# prominifinal.net
KiCad netlist of a schematic drawn in EAGLE
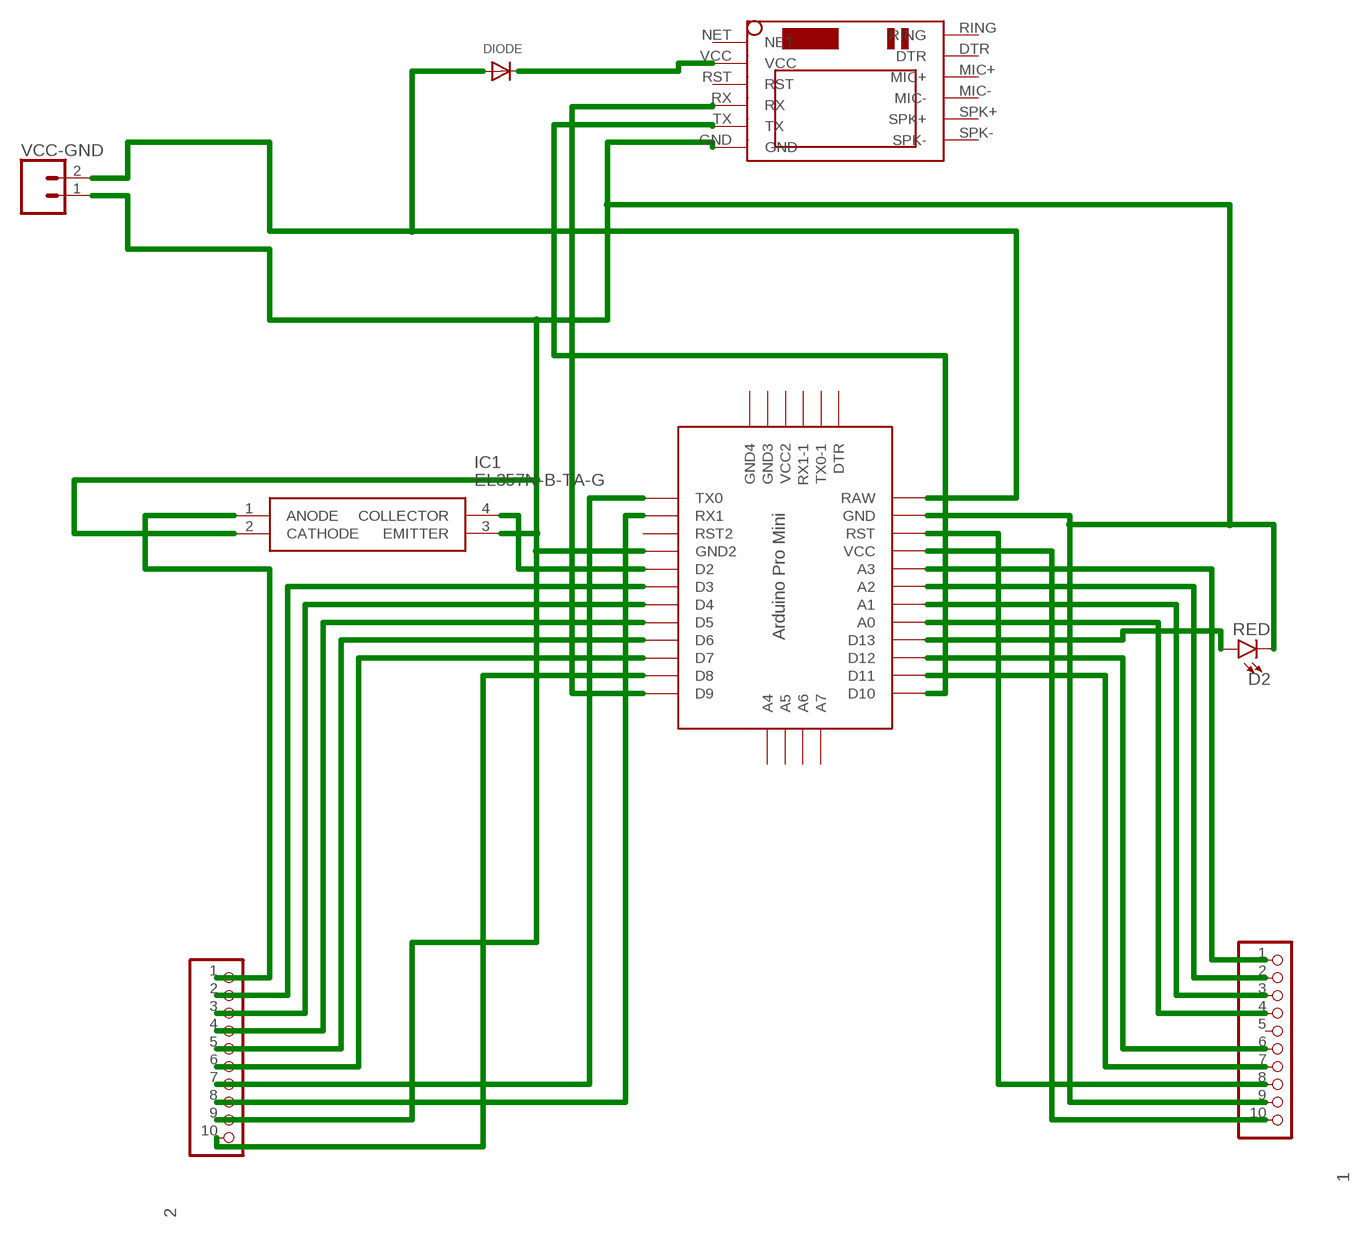
[diagram p0: schematic, sheet 1]

(export (version "E")
  (design (tool "Eeschema 10.0.6"))
  (components
    (comp (ref "1")
      (value "PINHD-1X10")
      (footprint "eagle-import:1X10")
      (libsource (lib "eagle-import") (part "PINHD-1X10"))
    )
    (comp (ref "2")
      (value "PINHD-1X10")
      (footprint "eagle-import:1X10")
      (libsource (lib "eagle-import") (part "PINHD-1X10"))
    )
    (comp (ref "D2")
      (value "RED")
      (footprint "eagle-import:LED-1206")
      (libsource (lib "eagle-import") (part "LED-RED1206"))
    )
    (comp (ref "DIODE")
      (value "DIODESOD-323F")
      (footprint "eagle-import:SOD-323F")
      (libsource (lib "eagle-import") (part "DIODESOD-323F"))
    )
    (comp (ref "IC1")
      (value "EL357N-B-TA-G")
      (footprint "eagle-import:SOP254P700X200-4N")
      (libsource (lib "eagle-import") (part "EL357N-B-TA-G"))
    )
    (comp (ref "PROMINI")
      (value "PRO-MINI")
      (footprint "eagle-import:PRO-MINI")
      (libsource (lib "eagle-import") (part "PRO-MINI"))
    )
    (comp (ref "U$1")
      (value "SIM800LMODULE")
      (footprint "eagle-import:SIM800LMODULE")
      (libsource (lib "eagle-import") (part "SIM800LMODULE"))
    )
    (comp (ref "VCC-GND")
      (value "CONN_025MM")
      (footprint "eagle-import:SCREWTERMINAL-5MM-2")
      (libsource (lib "eagle-import") (part "CONN_025MM"))
    )
  )
  (nets
    (net (code "1") (name "Net-(1-Pad1)") (class "Default")
      (node (ref "1") (pin "1") (pinfunction "1_1") (pintype "passive"))
      (node (ref "PROMINI") (pin "A3") (pinfunction "A3_A3") (pintype "bidirectional"))
    )
    (net (code "2") (name "Net-(1-Pad2)") (class "Default")
      (node (ref "1") (pin "2") (pinfunction "2_2") (pintype "passive"))
      (node (ref "PROMINI") (pin "A2") (pinfunction "A2_A2") (pintype "bidirectional"))
    )
    (net (code "3") (name "Net-(1-Pad3)") (class "Default")
      (node (ref "1") (pin "3") (pinfunction "3_3") (pintype "passive"))
      (node (ref "PROMINI") (pin "A1") (pinfunction "A1_A1") (pintype "bidirectional"))
    )
    (net (code "4") (name "Net-(1-Pad4)") (class "Default")
      (node (ref "1") (pin "4") (pinfunction "4_4") (pintype "passive"))
      (node (ref "PROMINI") (pin "A0") (pinfunction "A0_A0") (pintype "bidirectional"))
    )
    (net (code "5") (name "Net-(1-Pad6)") (class "Default")
      (node (ref "1") (pin "6") (pinfunction "6_6") (pintype "passive"))
      (node (ref "PROMINI") (pin "D12") (pinfunction "D12_D12") (pintype "bidirectional"))
    )
    (net (code "6") (name "Net-(1-Pad7)") (class "Default")
      (node (ref "1") (pin "7") (pinfunction "7_7") (pintype "passive"))
      (node (ref "PROMINI") (pin "D11") (pinfunction "D11_D11") (pintype "bidirectional"))
    )
    (net (code "7") (name "Net-(1-Pad8)") (class "Default")
      (node (ref "1") (pin "8") (pinfunction "8_8") (pintype "passive"))
      (node (ref "PROMINI") (pin "RST") (pinfunction "RST_RST") (pintype "bidirectional"))
    )
    (net (code "8") (name "Net-(1-Pad10)") (class "Default")
      (node (ref "1") (pin "10") (pinfunction "10_10") (pintype "passive"))
      (node (ref "PROMINI") (pin "VCC") (pinfunction "VCC_VCC") (pintype "bidirectional"))
    )
    (net (code "9") (name "Net-(2-Pad2)") (class "Default")
      (node (ref "2") (pin "2") (pinfunction "2_2") (pintype "passive"))
      (node (ref "PROMINI") (pin "D3") (pinfunction "D3_D3") (pintype "bidirectional"))
    )
    (net (code "10") (name "Net-(2-Pad3)") (class "Default")
      (node (ref "2") (pin "3") (pinfunction "3_3") (pintype "passive"))
      (node (ref "PROMINI") (pin "D4") (pinfunction "D4_D4") (pintype "bidirectional"))
    )
    (net (code "11") (name "Net-(2-Pad4)") (class "Default")
      (node (ref "2") (pin "4") (pinfunction "4_4") (pintype "passive"))
      (node (ref "PROMINI") (pin "D5") (pinfunction "D5_D5") (pintype "bidirectional"))
    )
    (net (code "12") (name "Net-(2-Pad5)") (class "Default")
      (node (ref "2") (pin "5") (pinfunction "5_5") (pintype "passive"))
      (node (ref "PROMINI") (pin "D6") (pinfunction "D6_D6") (pintype "bidirectional"))
    )
    (net (code "13") (name "Net-(2-Pad6)") (class "Default")
      (node (ref "2") (pin "6") (pinfunction "6_6") (pintype "passive"))
      (node (ref "PROMINI") (pin "D7") (pinfunction "D7_D7") (pintype "bidirectional"))
    )
    (net (code "14") (name "Net-(2-Pad7)") (class "Default")
      (node (ref "2") (pin "7") (pinfunction "7_7") (pintype "passive"))
      (node (ref "PROMINI") (pin "TX0") (pinfunction "TX0_TX0") (pintype "bidirectional"))
    )
    (net (code "15") (name "Net-(2-Pad8)") (class "Default")
      (node (ref "2") (pin "8") (pinfunction "8_8") (pintype "passive"))
      (node (ref "PROMINI") (pin "RX1") (pinfunction "RX1_RX1") (pintype "bidirectional"))
    )
    (net (code "16") (name "Net-(2-Pad10)") (class "Default")
      (node (ref "2") (pin "10") (pinfunction "10_10") (pintype "passive"))
      (node (ref "PROMINI") (pin "D8") (pinfunction "D8_D8") (pintype "bidirectional"))
    )
    (net (code "17") (name "Net-(D2-PadA)") (class "Default")
      (node (ref "D2") (pin "A") (pinfunction "A_A") (pintype "passive"))
      (node (ref "PROMINI") (pin "D13") (pinfunction "D13_D13") (pintype "bidirectional"))
    )
    (net (code "18") (name "Net-(DIODE-PadA)") (class "Default")
      (node (ref "DIODE") (pin "A") (pinfunction "A_A") (pintype "passive"))
      (node (ref "PROMINI") (pin "RAW") (pinfunction "RAW_RAW") (pintype "power_in"))
      (node (ref "VCC-GND") (pin "2") (pinfunction "2_2") (pintype "passive"))
    )
    (net (code "19") (name "Net-(DIODE-PadC)") (class "Default")
      (node (ref "DIODE") (pin "C") (pinfunction "C_C") (pintype "passive"))
      (node (ref "U$1") (pin "VCC") (pinfunction "VCC_VCC") (pintype "bidirectional"))
    )
    (net (code "20") (name "Net-(IC1-ANODE)") (class "Default")
      (node (ref "2") (pin "1") (pinfunction "1_1") (pintype "passive"))
      (node (ref "IC1") (pin "1") (pinfunction "ANODE_1") (pintype "bidirectional"))
    )
    (net (code "21") (name "Net-(IC1-CATHODE)") (class "Default")
      (node (ref "1") (pin "9") (pinfunction "9_9") (pintype "passive"))
      (node (ref "2") (pin "9") (pinfunction "9_9") (pintype "passive"))
      (node (ref "D2") (pin "C") (pinfunction "C_C") (pintype "passive"))
      (node (ref "IC1") (pin "2") (pinfunction "CATHODE_2") (pintype "bidirectional"))
      (node (ref "IC1") (pin "3") (pinfunction "EMITTER_3") (pintype "bidirectional"))
      (node (ref "PROMINI") (pin "GND") (pinfunction "GND_GND") (pintype "input"))
      (node (ref "PROMINI") (pin "GND1") (pinfunction "GND2_GND1") (pintype "bidirectional"))
      (node (ref "U$1") (pin "GND") (pinfunction "GND_GND") (pintype "bidirectional"))
      (node (ref "VCC-GND") (pin "1") (pinfunction "1_1") (pintype "passive"))
    )
    (net (code "22") (name "Net-(IC1-COLLECTOR)") (class "Default")
      (node (ref "IC1") (pin "4") (pinfunction "COLLECTOR_4") (pintype "bidirectional"))
      (node (ref "PROMINI") (pin "D2") (pinfunction "D2_D2") (pintype "bidirectional"))
    )
    (net (code "23") (name "Net-(PROMINI-PadD9)") (class "Default")
      (node (ref "PROMINI") (pin "D9") (pinfunction "D9_D9") (pintype "bidirectional"))
      (node (ref "U$1") (pin "RX") (pinfunction "RX_RX") (pintype "bidirectional"))
    )
    (net (code "24") (name "Net-(PROMINI-PadD10)") (class "Default")
      (node (ref "PROMINI") (pin "D10") (pinfunction "D10_D10") (pintype "bidirectional"))
      (node (ref "U$1") (pin "TX") (pinfunction "TX_TX") (pintype "bidirectional"))
    )
    (net (code "25") (name "unconnected-(1-Pad5)") (class "Default")
      (node (ref "1") (pin "5") (pinfunction "5_5") (pintype "passive"))
    )
    (net (code "26") (name "unconnected-(PROMINI-GND4-PadGND2)") (class "Default")
      (node (ref "PROMINI") (pin "GND2") (pinfunction "GND4_GND2") (pintype "bidirectional"))
    )
    (net (code "27") (name "unconnected-(PROMINI-PadA4)") (class "Default")
      (node (ref "PROMINI") (pin "A4") (pinfunction "A4_A4") (pintype "bidirectional"))
    )
    (net (code "28") (name "unconnected-(PROMINI-PadA5)") (class "Default")
      (node (ref "PROMINI") (pin "A5") (pinfunction "A5_A5") (pintype "bidirectional"))
    )
    (net (code "29") (name "unconnected-(PROMINI-PadA6)") (class "Default")
      (node (ref "PROMINI") (pin "A6") (pinfunction "A6_A6") (pintype "bidirectional"))
    )
    (net (code "30") (name "unconnected-(PROMINI-PadA7)") (class "Default")
      (node (ref "PROMINI") (pin "A7") (pinfunction "A7_A7") (pintype "bidirectional"))
    )
    (net (code "31") (name "unconnected-(PROMINI-PadDTR)") (class "Default")
      (node (ref "PROMINI") (pin "DTR") (pinfunction "DTR_DTR") (pintype "bidirectional"))
    )
    (net (code "32") (name "unconnected-(PROMINI-PadGND3)") (class "Default")
      (node (ref "PROMINI") (pin "GND3") (pinfunction "GND3_GND3") (pintype "bidirectional"))
    )
    (net (code "33") (name "unconnected-(PROMINI-PadRX1-1)") (class "Default")
      (node (ref "PROMINI") (pin "RX1-1") (pinfunction "RX1-1_RX1-1") (pintype "bidirectional"))
    )
    (net (code "34") (name "unconnected-(PROMINI-PadTX0-1)") (class "Default")
      (node (ref "PROMINI") (pin "TX0-1") (pinfunction "TX0-1_TX0-1") (pintype "bidirectional"))
    )
    (net (code "35") (name "unconnected-(PROMINI-RST2-PadRST1)") (class "Default")
      (node (ref "PROMINI") (pin "RST1") (pinfunction "RST2_RST1") (pintype "bidirectional"))
    )
    (net (code "36") (name "unconnected-(PROMINI-VCC2-PadVCC1)") (class "Default")
      (node (ref "PROMINI") (pin "VCC1") (pinfunction "VCC2_VCC1") (pintype "bidirectional"))
    )
    (net (code "37") (name "unconnected-(U$1-PadDTR)") (class "Default")
      (node (ref "U$1") (pin "DTR") (pinfunction "DTR_DTR") (pintype "bidirectional"))
    )
    (net (code "38") (name "unconnected-(U$1-PadMIC+)") (class "Default")
      (node (ref "U$1") (pin "MIC+") (pinfunction "MIC+_MIC+") (pintype "bidirectional"))
    )
    (net (code "39") (name "unconnected-(U$1-PadMIC-)") (class "Default")
      (node (ref "U$1") (pin "MIC-") (pinfunction "MIC-_MIC-") (pintype "bidirectional"))
    )
    (net (code "40") (name "unconnected-(U$1-PadNET)") (class "Default")
      (node (ref "U$1") (pin "NET") (pinfunction "NET_NET") (pintype "bidirectional"))
    )
    (net (code "41") (name "unconnected-(U$1-PadRING)") (class "Default")
      (node (ref "U$1") (pin "RING") (pinfunction "RING_RING") (pintype "bidirectional"))
    )
    (net (code "42") (name "unconnected-(U$1-PadRST)") (class "Default")
      (node (ref "U$1") (pin "RST") (pinfunction "RST_RST") (pintype "bidirectional"))
    )
    (net (code "43") (name "unconnected-(U$1-PadSPK+)") (class "Default")
      (node (ref "U$1") (pin "SPK+") (pinfunction "SPK+_SPK+") (pintype "bidirectional"))
    )
    (net (code "44") (name "unconnected-(U$1-PadSPK-)") (class "Default")
      (node (ref "U$1") (pin "SPK-") (pinfunction "SPK-_SPK-") (pintype "bidirectional"))
    )
  )
)
